# MicrocontrollerTwo.net
KiCad netlist of a schematic drawn in Altium Designer
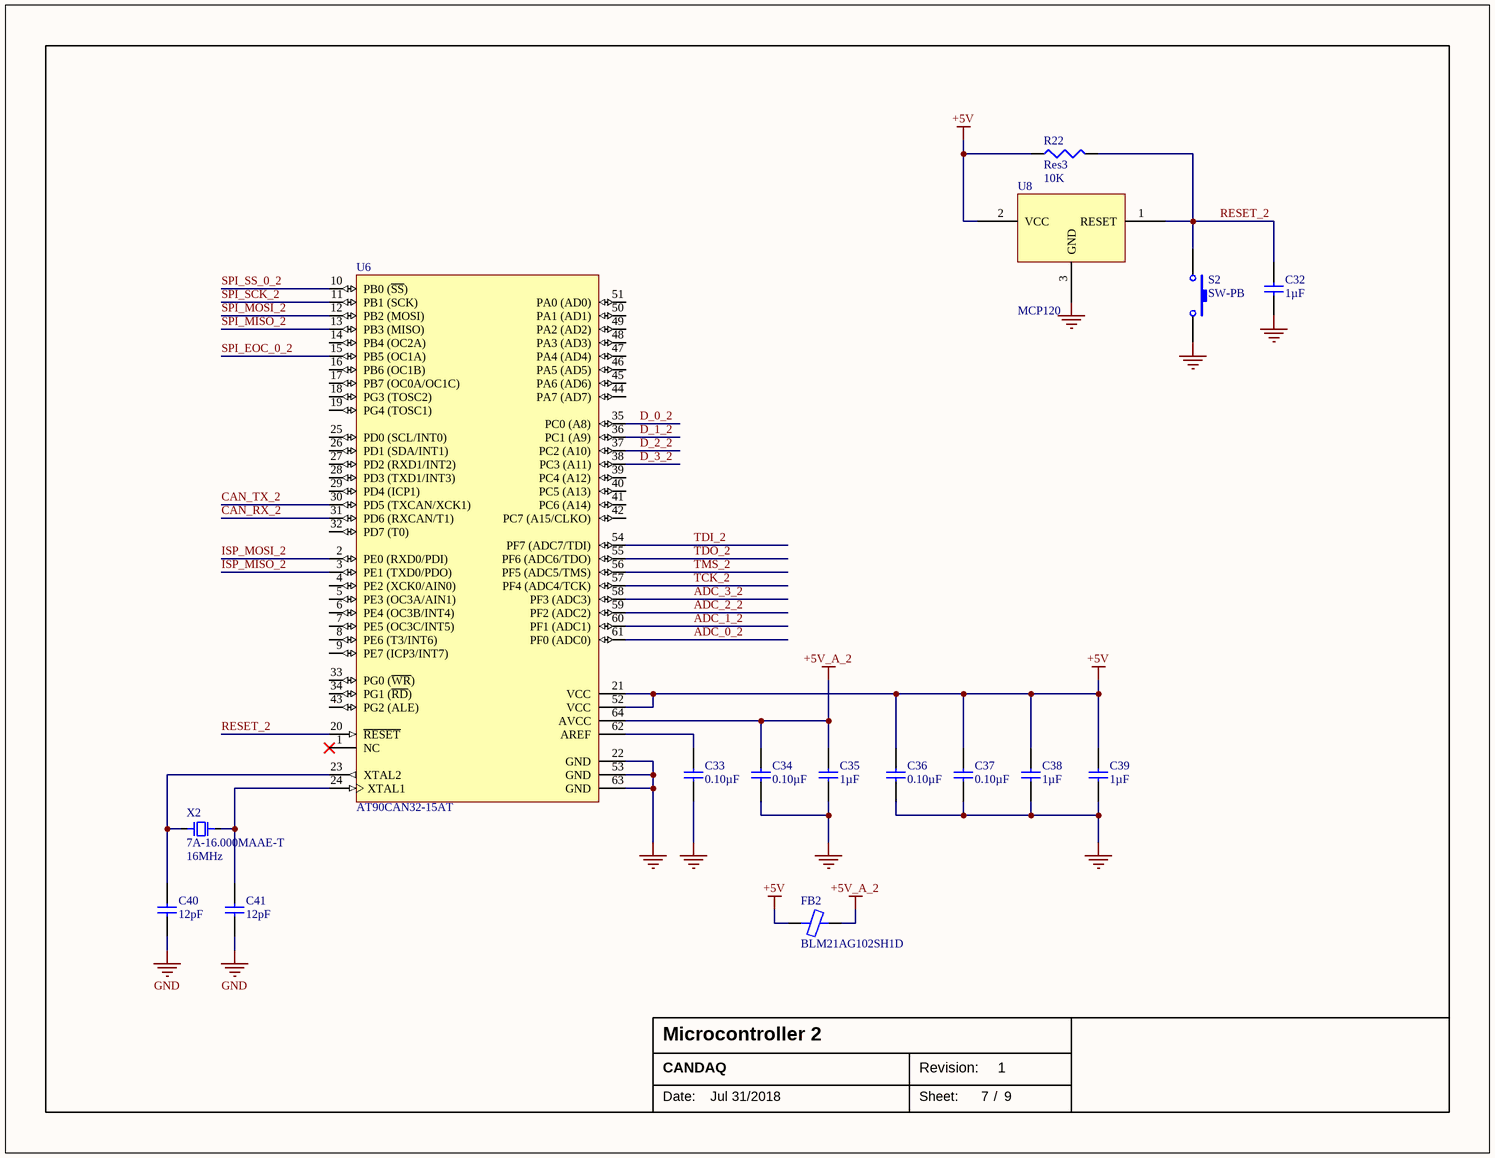
[diagram p0: MicrocontrollerTwo.SchDoc]

(export (version "E")
  (design (tool "Eeschema 10.0.6"))
  (components
    (comp (ref "C32")
      (value "1µF")
      (footprint "1206")
      (fields
        (field (name "PART NUMBER") "CC0805KKX7R7BB105")
        (field (name "TOLERANCE") "±10%")
        (field (name "VOLTAGE") "16V")
      )
      (libsource (lib "Capacitors") (part "Capacitor"))
    )
    (comp (ref "C33")
      (value "0.10µF")
      (footprint "1206")
      (fields
        (field (name "PART NUMBER") "CC0402KRX7R7BB104")
        (field (name "TOLERANCE") "±10%")
        (field (name "VOLTAGE") "16V")
      )
      (libsource (lib "Capacitors") (part "Capacitor"))
    )
    (comp (ref "C34")
      (value "0.10µF")
      (footprint "1206")
      (fields
        (field (name "PART NUMBER") "CC0402KRX7R7BB104")
        (field (name "TOLERANCE") "±10%")
        (field (name "VOLTAGE") "16V")
      )
      (libsource (lib "Capacitors") (part "Capacitor"))
    )
    (comp (ref "C35")
      (value "1µF")
      (footprint "1206")
      (fields
        (field (name "PART NUMBER") "CC0805KKX7R7BB105")
        (field (name "TOLERANCE") "±10%")
        (field (name "VOLTAGE") "16V")
      )
      (libsource (lib "Capacitors") (part "Capacitor"))
    )
    (comp (ref "C36")
      (value "0.10µF")
      (footprint "1206")
      (fields
        (field (name "PART NUMBER") "CC0402KRX7R7BB104")
        (field (name "TOLERANCE") "±10%")
        (field (name "VOLTAGE") "16V")
      )
      (libsource (lib "Capacitors") (part "Capacitor"))
    )
    (comp (ref "C37")
      (value "0.10µF")
      (footprint "1206")
      (fields
        (field (name "PART NUMBER") "CC0402KRX7R7BB104")
        (field (name "TOLERANCE") "±10%")
        (field (name "VOLTAGE") "16V")
      )
      (libsource (lib "Capacitors") (part "Capacitor"))
    )
    (comp (ref "C38")
      (value "1µF")
      (footprint "1206")
      (fields
        (field (name "PART NUMBER") "CC0805KKX7R7BB105")
        (field (name "TOLERANCE") "±10%")
        (field (name "VOLTAGE") "16V")
      )
      (libsource (lib "Capacitors") (part "Capacitor"))
    )
    (comp (ref "C39")
      (value "1µF")
      (footprint "1206")
      (fields
        (field (name "PART NUMBER") "CC0805KKX7R7BB105")
        (field (name "TOLERANCE") "±10%")
        (field (name "VOLTAGE") "16V")
      )
      (libsource (lib "Capacitors") (part "Capacitor"))
    )
    (comp (ref "C40")
      (value "12pF")
      (footprint "1206")
      (fields
        (field (name "PART NUMBER") "CC0402JRNPO9BN120")
        (field (name "TOLERANCE") "±5%")
        (field (name "VOLTAGE") "50V")
      )
      (libsource (lib "Capacitors") (part "Capacitor"))
    )
    (comp (ref "C41")
      (value "12pF")
      (footprint "1206")
      (fields
        (field (name "PART NUMBER") "CC0402JRNPO9BN120")
        (field (name "TOLERANCE") "±5%")
        (field (name "VOLTAGE") "50V")
      )
      (libsource (lib "Capacitors") (part "Capacitor"))
    )
    (comp (ref "FB2")
      (value "BLM21AG102SH1D")
      (footprint "INDC2012X11N")
      (libsource (lib "PDU-UV17") (part "BLM21AG102SH1D"))
    )
    (comp (ref "R22")
      (value "Res3")
      (footprint "1206")
      (description "Resistor")
      (fields (field (name "ALTIUM_VALUE") "10K") (field (name "PUBLISHER") "Altium Limited"))
      (libsource (lib "Miscellaneous Devices") (part "Res3"))
    )
    (comp (ref "S2")
      (value "SW-PB")
      (footprint "Switch")
      (description "Switch")
      (fields (field (name "PUBLISHER") "Altium Limited"))
      (libsource (lib "Miscellaneous Devices") (part "SW-PB"))
    )
    (comp (ref "U6")
      (value "AT90CAN32-15AT")
      (footprint "TQFP80P1600X1600X120-64N")
      (libsource (lib "PDU-UV17") (part "AT90CAN32-15AT"))
    )
    (comp (ref "U8") (value "MCP120") (footprint "MCP120") (libsource (lib "CANDAQ") (part "MCP120")))
    (comp (ref "X2")
      (value "7A-16.000MAAE-T")
      (footprint "QFN200P500X320X135-2N")
      (description "SMD Crystal Oscillator 12 pF")
      (fields (field (name "ALTIUM_VALUE") "16MHz"))
      (libsource (lib "PDUv2") (part "7A-16.000MAAE-T"))
    )
  )
  (nets
    (net (code "1") (name "+5V") (class "Default")
      (node (ref "C36") (pin "2") (pinfunction "2_2") (pintype "passive"))
      (node (ref "C37") (pin "2") (pinfunction "2_2") (pintype "passive"))
      (node (ref "C38") (pin "1") (pinfunction "1_1") (pintype "passive"))
      (node (ref "C39") (pin "1") (pinfunction "1_1") (pintype "passive"))
      (node (ref "FB2") (pin "1") (pinfunction "1_1") (pintype "passive"))
      (node (ref "R22") (pin "1") (pinfunction "1_1") (pintype "passive"))
      (node (ref "U6") (pin "21") (pinfunction "VCC_21") (pintype "power_in"))
      (node (ref "U6") (pin "52") (pinfunction "VCC_52") (pintype "power_in"))
      (node (ref "U8") (pin "2") (pinfunction "VCC_2") (pintype "passive"))
    )
    (net (code "2") (name "+5V_A_2") (class "Default")
      (node (ref "C34") (pin "2") (pinfunction "2_2") (pintype "passive"))
      (node (ref "C35") (pin "1") (pinfunction "1_1") (pintype "passive"))
      (node (ref "FB2") (pin "2") (pinfunction "2_2") (pintype "passive"))
      (node (ref "U6") (pin "64") (pinfunction "AVCC_64") (pintype "power_in"))
    )
    (net (code "3") (name "/ADC_0_2") (class "Default")
      (node (ref "U6") (pin "61") (pinfunction "PF0_(ADC0)_61") (pintype "bidirectional"))
    )
    (net (code "4") (name "/ADC_1_2") (class "Default")
      (node (ref "U6") (pin "60") (pinfunction "PF1_(ADC1)_60") (pintype "bidirectional"))
    )
    (net (code "5") (name "/ADC_2_2") (class "Default")
      (node (ref "U6") (pin "59") (pinfunction "PF2_(ADC2)_59") (pintype "bidirectional"))
    )
    (net (code "6") (name "/ADC_3_2") (class "Default")
      (node (ref "U6") (pin "58") (pinfunction "PF3_(ADC3)_58") (pintype "bidirectional"))
    )
    (net (code "7") (name "/CAN_RX_2") (class "Default")
      (node (ref "U6") (pin "31") (pinfunction "PD6_(RXCAN/T1)_31") (pintype "bidirectional"))
    )
    (net (code "8") (name "/CAN_TX_2") (class "Default")
      (node (ref "U6") (pin "30") (pinfunction "PD5_(TXCAN/XCK1)_30") (pintype "bidirectional"))
    )
    (net (code "9") (name "/D_0_2") (class "Default")
      (node (ref "U6") (pin "35") (pinfunction "PC0_(A8)_35") (pintype "bidirectional"))
    )
    (net (code "10") (name "/D_1_2") (class "Default")
      (node (ref "U6") (pin "36") (pinfunction "PC1_(A9)_36") (pintype "bidirectional"))
    )
    (net (code "11") (name "/D_2_2") (class "Default")
      (node (ref "U6") (pin "37") (pinfunction "PC2_(A10)_37") (pintype "bidirectional"))
    )
    (net (code "12") (name "/D_3_2") (class "Default")
      (node (ref "U6") (pin "38") (pinfunction "PC3_(A11)_38") (pintype "bidirectional"))
    )
    (net (code "13") (name "/ISP_MISO_2") (class "Default")
      (node (ref "U6") (pin "3") (pinfunction "PE1_(TXD0/PDO)_3") (pintype "bidirectional"))
    )
    (net (code "14") (name "/ISP_MOSI_2") (class "Default")
      (node (ref "U6") (pin "2") (pinfunction "PE0_(RXD0/PDI)_2") (pintype "bidirectional"))
    )
    (net (code "15") (name "/RESET_2") (class "Default")
      (node (ref "C32") (pin "1") (pinfunction "1_1") (pintype "passive"))
      (node (ref "R22") (pin "2") (pinfunction "2_2") (pintype "passive"))
      (node (ref "S2") (pin "1") (pinfunction "1_1") (pintype "passive"))
      (node (ref "U6") (pin "20") (pinfunction "~{RESET}_20") (pintype "input"))
      (node (ref "U8") (pin "1") (pinfunction "RESET_1") (pintype "passive"))
    )
    (net (code "16") (name "/SPI_EOC_0_2") (class "Default")
      (node (ref "U6") (pin "15") (pinfunction "PB5_(OC1A)_15") (pintype "bidirectional"))
    )
    (net (code "17") (name "/SPI_MISO_2") (class "Default")
      (node (ref "U6") (pin "13") (pinfunction "PB3_(MISO)_13") (pintype "bidirectional"))
    )
    (net (code "18") (name "/SPI_MOSI_2") (class "Default")
      (node (ref "U6") (pin "12") (pinfunction "PB2_(MOSI)_12") (pintype "bidirectional"))
    )
    (net (code "19") (name "/SPI_SCK_2") (class "Default")
      (node (ref "U6") (pin "11") (pinfunction "PB1_(SCK)_11") (pintype "bidirectional"))
    )
    (net (code "20") (name "/SPI_SS_0_2") (class "Default")
      (node (ref "U6") (pin "10") (pinfunction "PB0_(~{SS})_10") (pintype "bidirectional"))
    )
    (net (code "21") (name "/TCK_2") (class "Default")
      (node (ref "U6") (pin "57") (pinfunction "PF4_(ADC4/TCK)_57") (pintype "bidirectional"))
    )
    (net (code "22") (name "/TDI_2") (class "Default")
      (node (ref "U6") (pin "54") (pinfunction "PF7_(ADC7/TDI)_54") (pintype "bidirectional"))
    )
    (net (code "23") (name "/TDO_2") (class "Default")
      (node (ref "U6") (pin "55") (pinfunction "PF6_(ADC6/TDO)_55") (pintype "bidirectional"))
    )
    (net (code "24") (name "/TMS_2") (class "Default")
      (node (ref "U6") (pin "56") (pinfunction "PF5_(ADC5/TMS)_56") (pintype "bidirectional"))
    )
    (net (code "25") (name "GND") (class "Default")
      (node (ref "C32") (pin "2") (pinfunction "2_2") (pintype "passive"))
      (node (ref "C33") (pin "1") (pinfunction "1_1") (pintype "passive"))
      (node (ref "C34") (pin "1") (pinfunction "1_1") (pintype "passive"))
      (node (ref "C35") (pin "2") (pinfunction "2_2") (pintype "passive"))
      (node (ref "C36") (pin "1") (pinfunction "1_1") (pintype "passive"))
      (node (ref "C37") (pin "1") (pinfunction "1_1") (pintype "passive"))
      (node (ref "C38") (pin "2") (pinfunction "2_2") (pintype "passive"))
      (node (ref "C39") (pin "2") (pinfunction "2_2") (pintype "passive"))
      (node (ref "C40") (pin "1") (pinfunction "1_1") (pintype "passive"))
      (node (ref "C41") (pin "1") (pinfunction "1_1") (pintype "passive"))
      (node (ref "S2") (pin "2") (pinfunction "2_2") (pintype "passive"))
      (node (ref "U6") (pin "22") (pinfunction "GND_22") (pintype "power_in"))
      (node (ref "U6") (pin "53") (pinfunction "GND_53") (pintype "power_in"))
      (node (ref "U6") (pin "63") (pinfunction "GND_63") (pintype "power_in"))
      (node (ref "U8") (pin "3") (pinfunction "GND_3") (pintype "passive"))
    )
    (net (code "26") (name "Net-(U6-AREF)") (class "Default")
      (node (ref "C33") (pin "2") (pinfunction "2_2") (pintype "passive"))
      (node (ref "U6") (pin "62") (pinfunction "AREF_62") (pintype "power_in"))
    )
    (net (code "27") (name "Net-(U6-XTAL1)") (class "Default")
      (node (ref "C41") (pin "2") (pinfunction "2_2") (pintype "passive"))
      (node (ref "U6") (pin "24") (pinfunction "XTAL1_24") (pintype "input"))
      (node (ref "X2") (pin "2") (pinfunction "2_2") (pintype "passive"))
    )
    (net (code "28") (name "Net-(U6-XTAL2)") (class "Default")
      (node (ref "C40") (pin "2") (pinfunction "2_2") (pintype "passive"))
      (node (ref "U6") (pin "23") (pinfunction "XTAL2_23") (pintype "output"))
      (node (ref "X2") (pin "1") (pinfunction "1_1") (pintype "passive"))
    )
    (net (code "29") (name "unconnected-(U6-NC-Pad1)") (class "Default")
      (node (ref "U6") (pin "1") (pinfunction "NC_1") (pintype "passive+no_connect"))
    )
    (net (code "30") (name "unconnected-(U6-PA0_(AD0)-Pad51)") (class "Default")
      (node (ref "U6") (pin "51") (pinfunction "PA0_(AD0)_51") (pintype "bidirectional"))
    )
    (net (code "31") (name "unconnected-(U6-PA1_(AD1)-Pad50)") (class "Default")
      (node (ref "U6") (pin "50") (pinfunction "PA1_(AD1)_50") (pintype "bidirectional"))
    )
    (net (code "32") (name "unconnected-(U6-PA2_(AD2)-Pad49)") (class "Default")
      (node (ref "U6") (pin "49") (pinfunction "PA2_(AD2)_49") (pintype "bidirectional"))
    )
    (net (code "33") (name "unconnected-(U6-PA3_(AD3)-Pad48)") (class "Default")
      (node (ref "U6") (pin "48") (pinfunction "PA3_(AD3)_48") (pintype "bidirectional"))
    )
    (net (code "34") (name "unconnected-(U6-PA4_(AD4)-Pad47)") (class "Default")
      (node (ref "U6") (pin "47") (pinfunction "PA4_(AD4)_47") (pintype "bidirectional"))
    )
    (net (code "35") (name "unconnected-(U6-PA5_(AD5)-Pad46)") (class "Default")
      (node (ref "U6") (pin "46") (pinfunction "PA5_(AD5)_46") (pintype "bidirectional"))
    )
    (net (code "36") (name "unconnected-(U6-PA6_(AD6)-Pad45)") (class "Default")
      (node (ref "U6") (pin "45") (pinfunction "PA6_(AD6)_45") (pintype "bidirectional"))
    )
    (net (code "37") (name "unconnected-(U6-PA7_(AD7)-Pad44)") (class "Default")
      (node (ref "U6") (pin "44") (pinfunction "PA7_(AD7)_44") (pintype "bidirectional"))
    )
    (net (code "38") (name "unconnected-(U6-PB4_(OC2A)-Pad14)") (class "Default")
      (node (ref "U6") (pin "14") (pinfunction "PB4_(OC2A)_14") (pintype "bidirectional"))
    )
    (net (code "39") (name "unconnected-(U6-PB6_(OC1B)-Pad16)") (class "Default")
      (node (ref "U6") (pin "16") (pinfunction "PB6_(OC1B)_16") (pintype "bidirectional"))
    )
    (net (code "40") (name "unconnected-(U6-PB7_(OC0A{slash}OC1C)-Pad17)") (class "Default")
      (node (ref "U6") (pin "17") (pinfunction "PB7_(OC0A/OC1C)_17") (pintype "bidirectional"))
    )
    (net (code "41") (name "unconnected-(U6-PC4_(A12)-Pad39)") (class "Default")
      (node (ref "U6") (pin "39") (pinfunction "PC4_(A12)_39") (pintype "bidirectional"))
    )
    (net (code "42") (name "unconnected-(U6-PC5_(A13)-Pad40)") (class "Default")
      (node (ref "U6") (pin "40") (pinfunction "PC5_(A13)_40") (pintype "bidirectional"))
    )
    (net (code "43") (name "unconnected-(U6-PC6_(A14)-Pad41)") (class "Default")
      (node (ref "U6") (pin "41") (pinfunction "PC6_(A14)_41") (pintype "bidirectional"))
    )
    (net (code "44") (name "unconnected-(U6-PC7_(A15{slash}CLKO)-Pad42)") (class "Default")
      (node (ref "U6") (pin "42") (pinfunction "PC7_(A15/CLKO)_42") (pintype "bidirectional"))
    )
    (net (code "45") (name "unconnected-(U6-PD0_(SCL{slash}INT0)-Pad25)") (class "Default")
      (node (ref "U6") (pin "25") (pinfunction "PD0_(SCL/INT0)_25") (pintype "bidirectional"))
    )
    (net (code "46") (name "unconnected-(U6-PD1_(SDA{slash}INT1)-Pad26)") (class "Default")
      (node (ref "U6") (pin "26") (pinfunction "PD1_(SDA/INT1)_26") (pintype "bidirectional"))
    )
    (net (code "47") (name "unconnected-(U6-PD2_(RXD1{slash}INT2)-Pad27)") (class "Default")
      (node (ref "U6") (pin "27") (pinfunction "PD2_(RXD1/INT2)_27") (pintype "bidirectional"))
    )
    (net (code "48") (name "unconnected-(U6-PD3_(TXD1{slash}INT3)-Pad28)") (class "Default")
      (node (ref "U6") (pin "28") (pinfunction "PD3_(TXD1/INT3)_28") (pintype "bidirectional"))
    )
    (net (code "49") (name "unconnected-(U6-PD4_(ICP1)-Pad29)") (class "Default")
      (node (ref "U6") (pin "29") (pinfunction "PD4_(ICP1)_29") (pintype "bidirectional"))
    )
    (net (code "50") (name "unconnected-(U6-PD7_(T0)-Pad32)") (class "Default")
      (node (ref "U6") (pin "32") (pinfunction "PD7_(T0)_32") (pintype "bidirectional"))
    )
    (net (code "51") (name "unconnected-(U6-PE2_(XCK0{slash}AIN0)-Pad4)") (class "Default")
      (node (ref "U6") (pin "4") (pinfunction "PE2_(XCK0/AIN0)_4") (pintype "bidirectional"))
    )
    (net (code "52") (name "unconnected-(U6-PE3_(OC3A{slash}AIN1)-Pad5)") (class "Default")
      (node (ref "U6") (pin "5") (pinfunction "PE3_(OC3A/AIN1)_5") (pintype "bidirectional"))
    )
    (net (code "53") (name "unconnected-(U6-PE4_(OC3B{slash}INT4)-Pad6)") (class "Default")
      (node (ref "U6") (pin "6") (pinfunction "PE4_(OC3B/INT4)_6") (pintype "bidirectional"))
    )
    (net (code "54") (name "unconnected-(U6-PE5_(OC3C{slash}INT5)-Pad7)") (class "Default")
      (node (ref "U6") (pin "7") (pinfunction "PE5_(OC3C/INT5)_7") (pintype "bidirectional"))
    )
    (net (code "55") (name "unconnected-(U6-PE6_(T3{slash}INT6)-Pad8)") (class "Default")
      (node (ref "U6") (pin "8") (pinfunction "PE6_(T3/INT6)_8") (pintype "bidirectional"))
    )
    (net (code "56") (name "unconnected-(U6-PE7_(ICP3{slash}INT7)-Pad9)") (class "Default")
      (node (ref "U6") (pin "9") (pinfunction "PE7_(ICP3/INT7)_9") (pintype "bidirectional"))
    )
    (net (code "57") (name "unconnected-(U6-PG0_(~{WR})-Pad33)") (class "Default")
      (node (ref "U6") (pin "33") (pinfunction "PG0_(~{WR})_33") (pintype "bidirectional"))
    )
    (net (code "58") (name "unconnected-(U6-PG1_(~{RD})-Pad34)") (class "Default")
      (node (ref "U6") (pin "34") (pinfunction "PG1_(~{RD})_34") (pintype "bidirectional"))
    )
    (net (code "59") (name "unconnected-(U6-PG2_(ALE)-Pad43)") (class "Default")
      (node (ref "U6") (pin "43") (pinfunction "PG2_(ALE)_43") (pintype "bidirectional"))
    )
    (net (code "60") (name "unconnected-(U6-PG3_(TOSC2)-Pad18)") (class "Default")
      (node (ref "U6") (pin "18") (pinfunction "PG3_(TOSC2)_18") (pintype "bidirectional"))
    )
    (net (code "61") (name "unconnected-(U6-PG4_(TOSC1)-Pad19)") (class "Default")
      (node (ref "U6") (pin "19") (pinfunction "PG4_(TOSC1)_19") (pintype "bidirectional"))
    )
  )
)
